# servo.net
KiCad netlist of a schematic drawn in Altium Designer
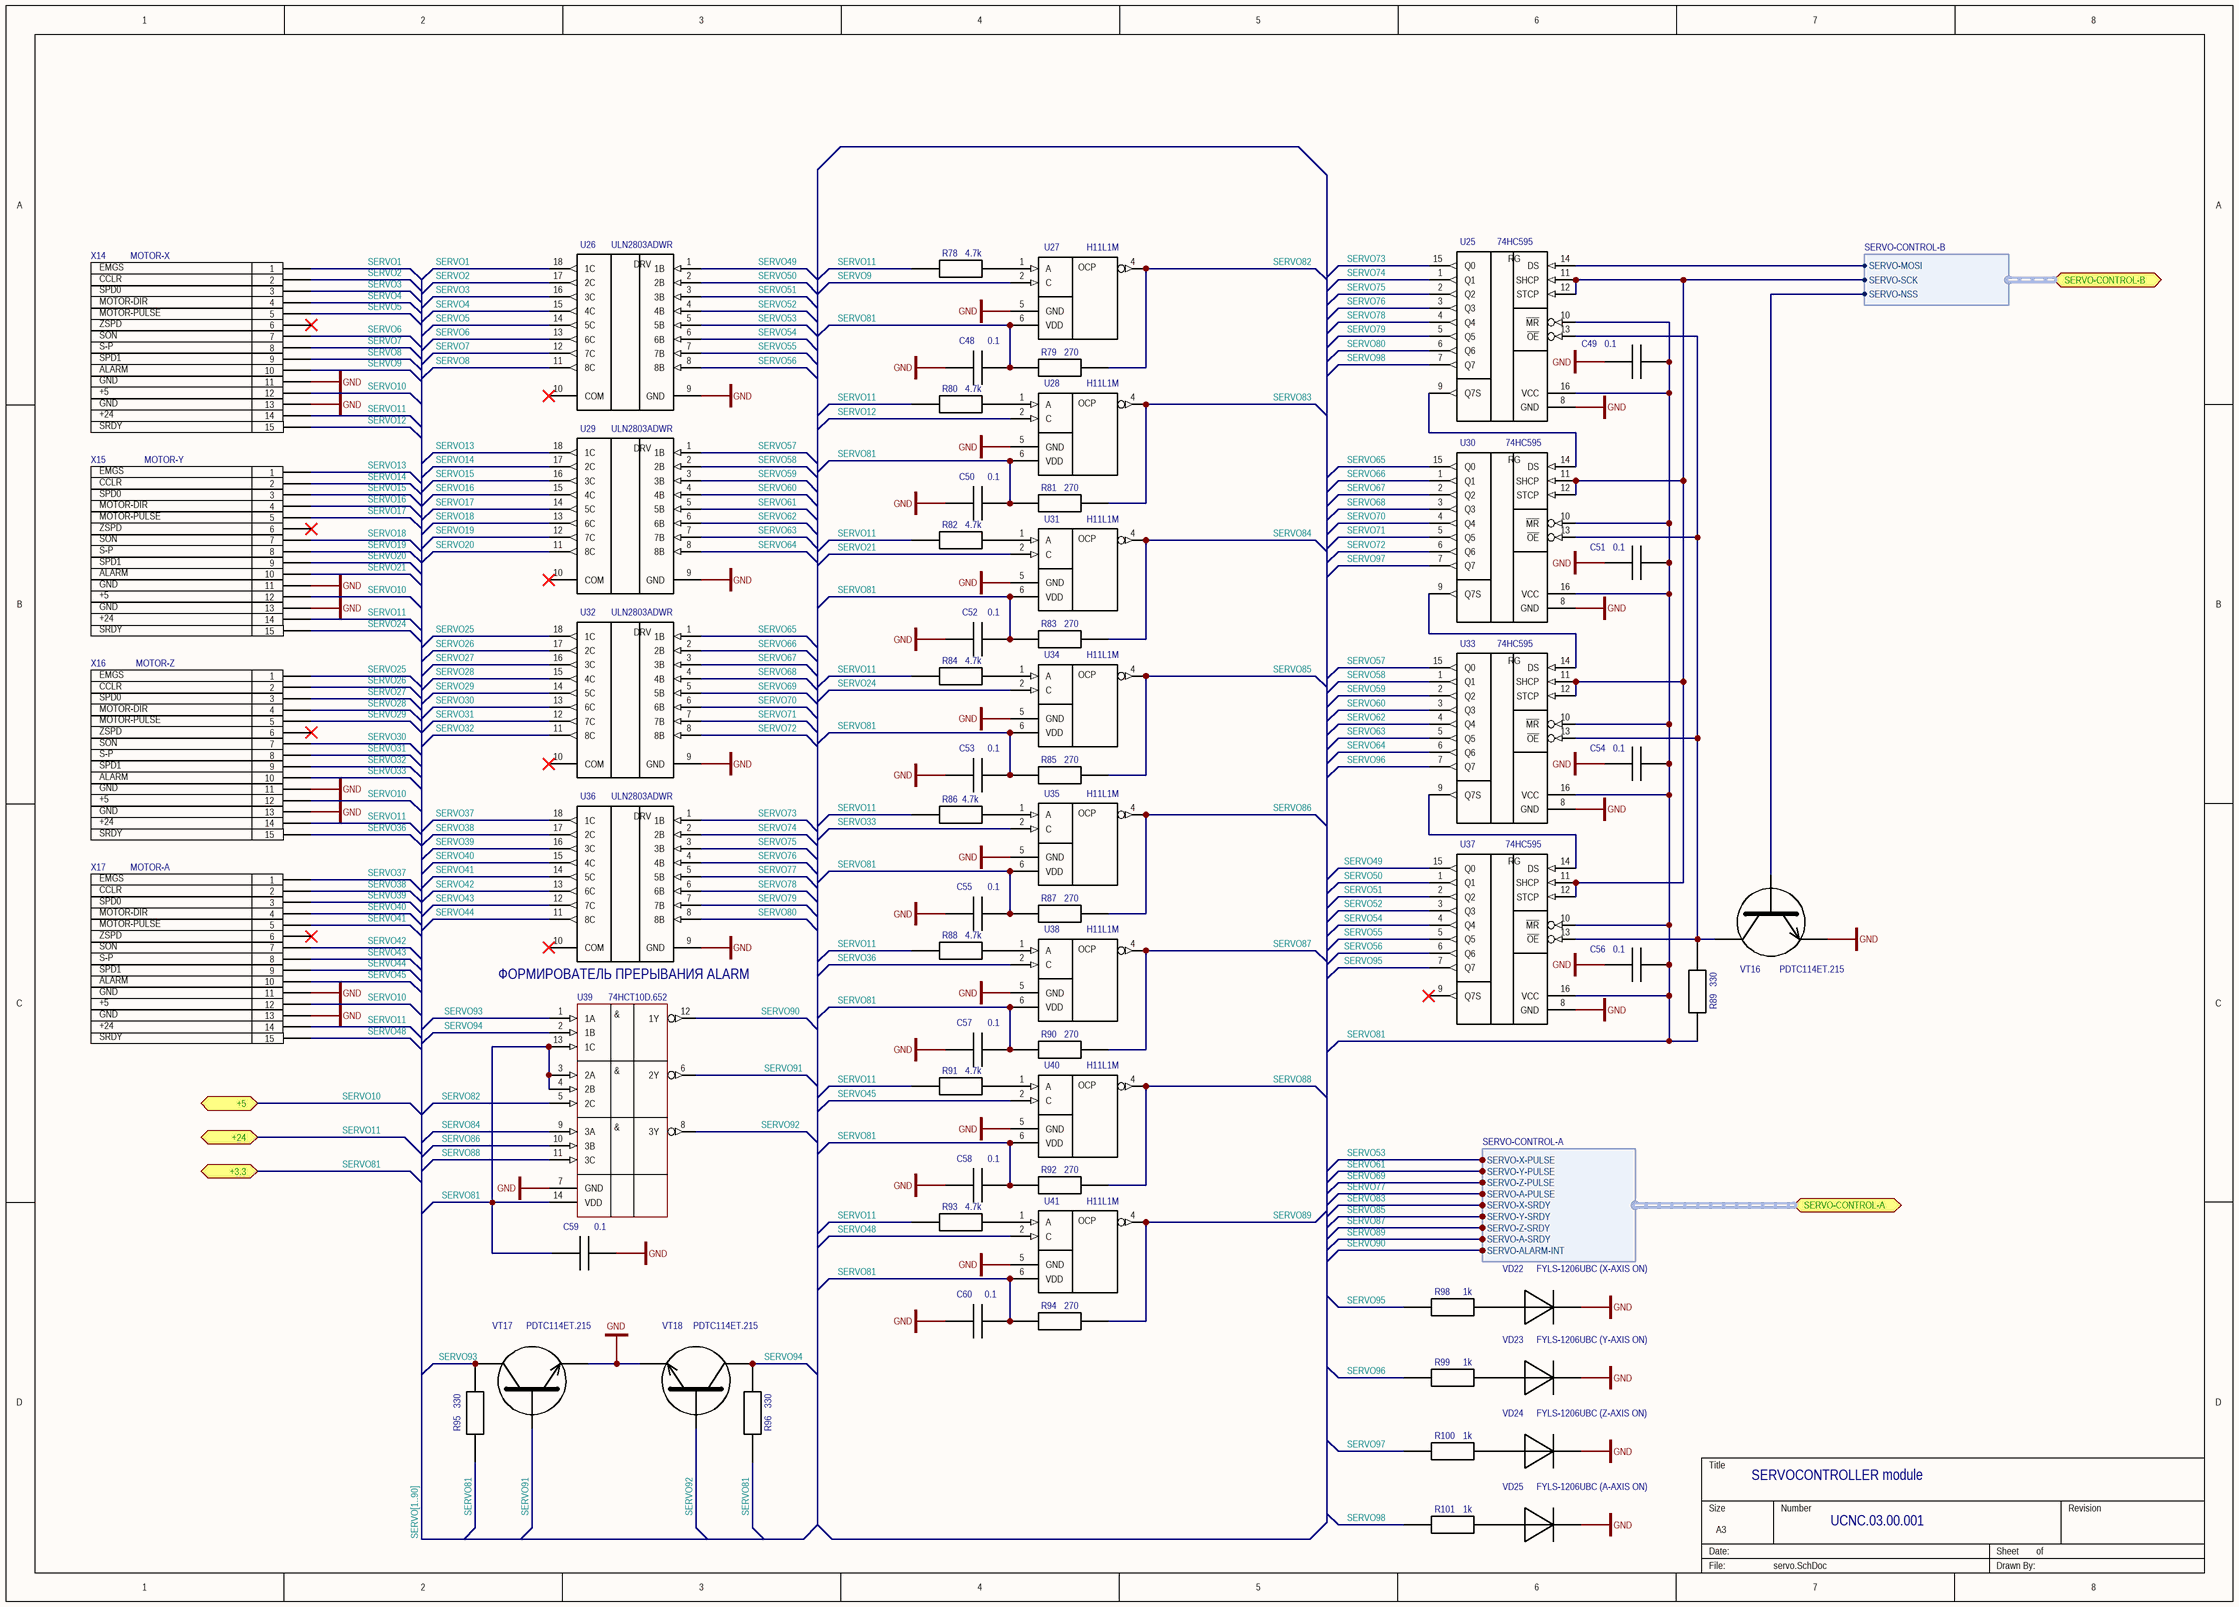
[diagram p0: servo.SchDoc]

(export (version "E")
  (design (tool "Eeschema 10.0.6"))
  (components
    (comp (ref "C48")
      (value "0.1")
      (footprint "CAPC2012X04N")
      (description "SMD конденсатор")
      (libsource (lib "ulysses_library") (part "C"))
    )
    (comp (ref "C49")
      (value "0.1")
      (footprint "CAPC2012X04N")
      (description "SMD конденсатор")
      (libsource (lib "ulysses_library") (part "C"))
    )
    (comp (ref "C50")
      (value "0.1")
      (footprint "CAPC2012X04N")
      (description "SMD конденсатор")
      (libsource (lib "ulysses_library") (part "C"))
    )
    (comp (ref "C51")
      (value "0.1")
      (footprint "CAPC2012X04N")
      (description "SMD конденсатор")
      (libsource (lib "ulysses_library") (part "C"))
    )
    (comp (ref "C52")
      (value "0.1")
      (footprint "CAPC2012X04N")
      (description "SMD конденсатор")
      (libsource (lib "ulysses_library") (part "C"))
    )
    (comp (ref "C53")
      (value "0.1")
      (footprint "CAPC2012X04N")
      (description "SMD конденсатор")
      (libsource (lib "ulysses_library") (part "C"))
    )
    (comp (ref "C54")
      (value "0.1")
      (footprint "CAPC2012X04N")
      (description "SMD конденсатор")
      (libsource (lib "ulysses_library") (part "C"))
    )
    (comp (ref "C55")
      (value "0.1")
      (footprint "CAPC2012X04N")
      (description "SMD конденсатор")
      (libsource (lib "ulysses_library") (part "C"))
    )
    (comp (ref "C56")
      (value "0.1")
      (footprint "CAPC2012X04N")
      (description "SMD конденсатор")
      (libsource (lib "ulysses_library") (part "C"))
    )
    (comp (ref "C57")
      (value "0.1")
      (footprint "CAPC2012X04N")
      (description "SMD конденсатор")
      (libsource (lib "ulysses_library") (part "C"))
    )
    (comp (ref "C58")
      (value "0.1")
      (footprint "CAPC2012X04N")
      (description "SMD конденсатор")
      (libsource (lib "ulysses_library") (part "C"))
    )
    (comp (ref "C59")
      (value "0.1")
      (footprint "CAPC2012X04N")
      (description "SMD конденсатор")
      (libsource (lib "ulysses_library") (part "C"))
    )
    (comp (ref "C60")
      (value "0.1")
      (footprint "CAPC2012X04N")
      (description "SMD конденсатор")
      (libsource (lib "ulysses_library") (part "C"))
    )
    (comp (ref "R78")
      (value "4.7k")
      (footprint "RESC2012X04N")
      (description "SMD резистор")
      (libsource (lib "ulysses_library") (part "R"))
    )
    (comp (ref "R79")
      (value "270")
      (footprint "RESC2012X04N")
      (description "SMD резистор")
      (libsource (lib "ulysses_library") (part "R"))
    )
    (comp (ref "R80")
      (value "4.7k")
      (footprint "RESC2012X04N")
      (description "SMD резистор")
      (libsource (lib "ulysses_library") (part "R"))
    )
    (comp (ref "R81")
      (value "270")
      (footprint "RESC2012X04N")
      (description "SMD резистор")
      (libsource (lib "ulysses_library") (part "R"))
    )
    (comp (ref "R82")
      (value "4.7k")
      (footprint "RESC2012X04N")
      (description "SMD резистор")
      (libsource (lib "ulysses_library") (part "R"))
    )
    (comp (ref "R83")
      (value "270")
      (footprint "RESC2012X04N")
      (description "SMD резистор")
      (libsource (lib "ulysses_library") (part "R"))
    )
    (comp (ref "R84")
      (value "4.7k")
      (footprint "RESC2012X04N")
      (description "SMD резистор")
      (libsource (lib "ulysses_library") (part "R"))
    )
    (comp (ref "R85")
      (value "270")
      (footprint "RESC2012X04N")
      (description "SMD резистор")
      (libsource (lib "ulysses_library") (part "R"))
    )
    (comp (ref "R86")
      (value "4.7k")
      (footprint "RESC2012X04N")
      (description "SMD резистор")
      (libsource (lib "ulysses_library") (part "R"))
    )
    (comp (ref "R87")
      (value "270")
      (footprint "RESC2012X04N")
      (description "SMD резистор")
      (libsource (lib "ulysses_library") (part "R"))
    )
    (comp (ref "R88")
      (value "4.7k")
      (footprint "RESC2012X04N")
      (description "SMD резистор")
      (libsource (lib "ulysses_library") (part "R"))
    )
    (comp (ref "R89")
      (value "330")
      (footprint "RESC1608X05N")
      (description "SMD резистор")
      (libsource (lib "ulysses_library") (part "R"))
    )
    (comp (ref "R90")
      (value "270")
      (footprint "RESC2012X04N")
      (description "SMD резистор")
      (libsource (lib "ulysses_library") (part "R"))
    )
    (comp (ref "R91")
      (value "4.7k")
      (footprint "RESC2012X04N")
      (description "SMD резистор")
      (libsource (lib "ulysses_library") (part "R"))
    )
    (comp (ref "R92")
      (value "270")
      (footprint "RESC2012X04N")
      (description "SMD резистор")
      (libsource (lib "ulysses_library") (part "R"))
    )
    (comp (ref "R93")
      (value "4.7k")
      (footprint "RESC2012X04N")
      (description "SMD резистор")
      (libsource (lib "ulysses_library") (part "R"))
    )
    (comp (ref "R94")
      (value "270")
      (footprint "RESC2012X04N")
      (description "SMD резистор")
      (libsource (lib "ulysses_library") (part "R"))
    )
    (comp (ref "R95")
      (value "330")
      (footprint "RESC2012X04N")
      (description "SMD резистор")
      (libsource (lib "ulysses_library") (part "R"))
    )
    (comp (ref "R96")
      (value "330")
      (footprint "RESC2012X04N")
      (description "SMD резистор")
      (libsource (lib "ulysses_library") (part "R"))
    )
    (comp (ref "R98")
      (value "1k")
      (footprint "RESC2012X04N")
      (description "SMD резистор")
      (libsource (lib "ulysses_library") (part "R"))
    )
    (comp (ref "R99")
      (value "1k")
      (footprint "RESC2012X04N")
      (description "SMD резистор")
      (libsource (lib "ulysses_library") (part "R"))
    )
    (comp (ref "R100")
      (value "1k")
      (footprint "RESC2012X04N")
      (description "SMD резистор")
      (libsource (lib "ulysses_library") (part "R"))
    )
    (comp (ref "R101")
      (value "1k")
      (footprint "RESC2012X04N")
      (description "SMD резистор")
      (libsource (lib "ulysses_library") (part "R"))
    )
    (comp (ref "U25")
      (value "74HC595")
      (footprint "SOP127P700X210-16N")
      (libsource (lib "ulysses_library") (part "74HC595"))
    )
    (comp (ref "U26")
      (value "ULN2803ADWR")
      (footprint "SOIC127P1030X265-18N")
      (description "8 Darlington transistors")
      (libsource (lib "ulysses_library") (part "ULN2803ADWR"))
    )
    (comp (ref "U27")
      (value "H11L1M")
      (footprint "DIP6")
      (description "Fairchild H11L1M Schmitt Trigger Output Optocoupler")
      (libsource (lib "ulysses_library") (part "H11L1M"))
    )
    (comp (ref "U28")
      (value "H11L1M")
      (footprint "DIP6")
      (description "Fairchild H11L1M Schmitt Trigger Output Optocoupler")
      (libsource (lib "ulysses_library") (part "H11L1M"))
    )
    (comp (ref "U29")
      (value "ULN2803ADWR")
      (footprint "SOIC127P1030X265-18N")
      (description "8 Darlington transistors")
      (libsource (lib "ulysses_library") (part "ULN2803ADWR"))
    )
    (comp (ref "U30")
      (value "74HC595")
      (footprint "SOP127P700X210-16N")
      (libsource (lib "ulysses_library") (part "74HC595"))
    )
    (comp (ref "U31")
      (value "H11L1M")
      (footprint "DIP6")
      (description "Fairchild H11L1M Schmitt Trigger Output Optocoupler")
      (libsource (lib "ulysses_library") (part "H11L1M"))
    )
    (comp (ref "U32")
      (value "ULN2803ADWR")
      (footprint "SOIC127P1030X265-18N")
      (description "8 Darlington transistors")
      (libsource (lib "ulysses_library") (part "ULN2803ADWR"))
    )
    (comp (ref "U33")
      (value "74HC595")
      (footprint "SOP127P700X210-16N")
      (libsource (lib "ulysses_library") (part "74HC595"))
    )
    (comp (ref "U34")
      (value "H11L1M")
      (footprint "DIP6")
      (description "Fairchild H11L1M Schmitt Trigger Output Optocoupler")
      (libsource (lib "ulysses_library") (part "H11L1M"))
    )
    (comp (ref "U35")
      (value "H11L1M")
      (footprint "DIP6")
      (description "Fairchild H11L1M Schmitt Trigger Output Optocoupler")
      (libsource (lib "ulysses_library") (part "H11L1M"))
    )
    (comp (ref "U36")
      (value "ULN2803ADWR")
      (footprint "SOIC127P1030X265-18N")
      (description "8 Darlington transistors")
      (libsource (lib "ulysses_library") (part "ULN2803ADWR"))
    )
    (comp (ref "U37")
      (value "74HC595")
      (footprint "SOP127P700X210-16N")
      (libsource (lib "ulysses_library") (part "74HC595"))
    )
    (comp (ref "U38")
      (value "H11L1M")
      (footprint "DIP6")
      (description "Fairchild H11L1M Schmitt Trigger Output Optocoupler")
      (libsource (lib "ulysses_library") (part "H11L1M"))
    )
    (comp (ref "U39")
      (value "74HCT10D.652")
      (footprint "SOIC127P600X175-14N")
      (libsource (lib "ulysses_library") (part "74HCT10D.652"))
    )
    (comp (ref "U40")
      (value "H11L1M")
      (footprint "DIP6")
      (description "Fairchild H11L1M Schmitt Trigger Output Optocoupler")
      (libsource (lib "ulysses_library") (part "H11L1M"))
    )
    (comp (ref "U41")
      (value "H11L1M")
      (footprint "DIP6")
      (description "Fairchild H11L1M Schmitt Trigger Output Optocoupler")
      (libsource (lib "ulysses_library") (part "H11L1M"))
    )
    (comp (ref "VD22")
      (value "FYLS-1206UBC (X-AXIS ON)")
      (footprint "CAPMP3216X11N")
      (description "Светодиод")
      (libsource (lib "ulysses_library") (part "FYLS-1206"))
    )
    (comp (ref "VD23")
      (value "FYLS-1206UBC (Y-AXIS ON)")
      (footprint "CAPMP3216X11N")
      (description "Светодиод")
      (libsource (lib "ulysses_library") (part "FYLS-1206"))
    )
    (comp (ref "VD24")
      (value "FYLS-1206UBC (Z-AXIS ON)")
      (footprint "CAPMP3216X11N")
      (description "Светодиод")
      (libsource (lib "ulysses_library") (part "FYLS-1206"))
    )
    (comp (ref "VD25")
      (value "FYLS-1206UBC (A-AXIS ON)")
      (footprint "CAPMP3216X11N")
      (description "Светодиод")
      (libsource (lib "ulysses_library") (part "FYLS-1206"))
    )
    (comp (ref "VT16")
      (value "PDTC114ET.215")
      (footprint "SOT95P238X102-3N")
      (description "NPN transistor with bias circuit")
      (libsource (lib "ulysses_library") (part "PDTC114ET.215"))
    )
    (comp (ref "VT17")
      (value "PDTC114ET.215")
      (footprint "SOT95P238X102-3N")
      (description "NPN transistor with bias circuit")
      (libsource (lib "") (part "PDTC114ET.215_1"))
    )
    (comp (ref "VT18")
      (value "PDTC114ET.215")
      (footprint "SOT95P238X102-3N")
      (description "NPN transistor with bias circuit")
      (libsource (lib "ulysses_library") (part "PDTC114ET.215"))
    )
    (comp (ref "X14")
      (value "MOTOR-X")
      (footprint "DMR15F-HD")
      (libsource (lib "ulysses_library") (part "DMR15F-HD"))
    )
    (comp (ref "X15")
      (value "MOTOR-Y")
      (footprint "DMR15F-HD")
      (libsource (lib "ulysses_library") (part "DMR15F-HD"))
    )
    (comp (ref "X16")
      (value "MOTOR-Z")
      (footprint "DMR15F-HD")
      (libsource (lib "ulysses_library") (part "DMR15F-HD"))
    )
    (comp (ref "X17")
      (value "MOTOR-A")
      (footprint "DMR15F-HD")
      (libsource (lib "ulysses_library") (part "DMR15F-HD"))
    )
  )
  (nets
    (net (code "9") (name "/SERVO-MOSI") (class "Default")
      (node (ref "U25") (pin "14") (pinfunction "DS_14") (pintype "input"))
    )
    (net (code "10") (name "/SERVO-NSS") (class "Default")
      (node (ref "VT16") (pin "1") (pinfunction "B_1") (pintype "power_in"))
    )
    (net (code "11") (name "/SERVO-SCK") (class "Default")
      (node (ref "U25") (pin "11") (pinfunction "SHCP_11") (pintype "input"))
      (node (ref "U25") (pin "12") (pinfunction "STCP_12") (pintype "input"))
      (node (ref "U30") (pin "11") (pinfunction "SHCP_11") (pintype "input"))
      (node (ref "U30") (pin "12") (pinfunction "STCP_12") (pintype "input"))
      (node (ref "U33") (pin "11") (pinfunction "SHCP_11") (pintype "input"))
      (node (ref "U33") (pin "12") (pinfunction "STCP_12") (pintype "input"))
      (node (ref "U37") (pin "11") (pinfunction "SHCP_11") (pintype "input"))
      (node (ref "U37") (pin "12") (pinfunction "STCP_12") (pintype "input"))
    )
    (net (code "12") (name "/SERVO1") (class "Default")
      (node (ref "U26") (pin "18") (pinfunction "1C_18") (pintype "output"))
      (node (ref "X14") (pin "1") (pinfunction "1_1") (pintype "passive"))
    )
    (net (code "13") (name "/SERVO2") (class "Default")
      (node (ref "U26") (pin "17") (pinfunction "2C_17") (pintype "output"))
      (node (ref "X14") (pin "2") (pinfunction "2_2") (pintype "passive"))
    )
    (net (code "14") (name "/SERVO3") (class "Default")
      (node (ref "U26") (pin "16") (pinfunction "3C_16") (pintype "output"))
      (node (ref "X14") (pin "3") (pinfunction "3_3") (pintype "passive"))
    )
    (net (code "15") (name "/SERVO4") (class "Default")
      (node (ref "U26") (pin "15") (pinfunction "4C_15") (pintype "output"))
      (node (ref "X14") (pin "4") (pinfunction "4_4") (pintype "passive"))
    )
    (net (code "16") (name "/SERVO5") (class "Default")
      (node (ref "U26") (pin "14") (pinfunction "5C_14") (pintype "output"))
      (node (ref "X14") (pin "5") (pinfunction "5_5") (pintype "passive"))
    )
    (net (code "17") (name "/SERVO6") (class "Default")
      (node (ref "U26") (pin "13") (pinfunction "6C_13") (pintype "output"))
      (node (ref "X14") (pin "7") (pinfunction "7_7") (pintype "passive"))
    )
    (net (code "18") (name "/SERVO7") (class "Default")
      (node (ref "U26") (pin "12") (pinfunction "7C_12") (pintype "output"))
      (node (ref "X14") (pin "8") (pinfunction "8_8") (pintype "passive"))
    )
    (net (code "19") (name "/SERVO8") (class "Default")
      (node (ref "U26") (pin "11") (pinfunction "8C_11") (pintype "output"))
      (node (ref "X14") (pin "9") (pinfunction "9_9") (pintype "passive"))
    )
    (net (code "20") (name "/SERVO9") (class "Default")
      (node (ref "U27") (pin "2") (pinfunction "C_2") (pintype "input"))
      (node (ref "X14") (pin "10") (pinfunction "10_10") (pintype "passive"))
    )
    (net (code "21") (name "/SERVO10") (class "Default")
      (node (ref "X14") (pin "12") (pinfunction "12_12") (pintype "passive"))
      (node (ref "X15") (pin "12") (pinfunction "12_12") (pintype "passive"))
      (node (ref "X16") (pin "12") (pinfunction "12_12") (pintype "passive"))
      (node (ref "X17") (pin "12") (pinfunction "12_12") (pintype "passive"))
    )
    (net (code "22") (name "/SERVO11") (class "Default")
      (node (ref "R78") (pin "1") (pintype "passive"))
      (node (ref "R80") (pin "1") (pintype "passive"))
      (node (ref "R82") (pin "1") (pintype "passive"))
      (node (ref "R84") (pin "1") (pintype "passive"))
      (node (ref "R86") (pin "1") (pintype "passive"))
      (node (ref "R88") (pin "1") (pintype "passive"))
      (node (ref "R91") (pin "1") (pintype "passive"))
      (node (ref "R93") (pin "1") (pintype "passive"))
      (node (ref "X14") (pin "14") (pinfunction "14_14") (pintype "passive"))
      (node (ref "X15") (pin "14") (pinfunction "14_14") (pintype "passive"))
      (node (ref "X16") (pin "14") (pinfunction "14_14") (pintype "passive"))
      (node (ref "X17") (pin "14") (pinfunction "14_14") (pintype "passive"))
    )
    (net (code "23") (name "/SERVO12") (class "Default")
      (node (ref "U28") (pin "2") (pinfunction "C_2") (pintype "input"))
      (node (ref "X14") (pin "15") (pinfunction "15_15") (pintype "passive"))
    )
    (net (code "24") (name "/SERVO13") (class "Default")
      (node (ref "U29") (pin "18") (pinfunction "1C_18") (pintype "output"))
      (node (ref "X15") (pin "1") (pinfunction "1_1") (pintype "passive"))
    )
    (net (code "25") (name "/SERVO14") (class "Default")
      (node (ref "U29") (pin "17") (pinfunction "2C_17") (pintype "output"))
      (node (ref "X15") (pin "2") (pinfunction "2_2") (pintype "passive"))
    )
    (net (code "26") (name "/SERVO15") (class "Default")
      (node (ref "U29") (pin "16") (pinfunction "3C_16") (pintype "output"))
      (node (ref "X15") (pin "3") (pinfunction "3_3") (pintype "passive"))
    )
    (net (code "27") (name "/SERVO16") (class "Default")
      (node (ref "U29") (pin "15") (pinfunction "4C_15") (pintype "output"))
      (node (ref "X15") (pin "4") (pinfunction "4_4") (pintype "passive"))
    )
    (net (code "28") (name "/SERVO17") (class "Default")
      (node (ref "U29") (pin "14") (pinfunction "5C_14") (pintype "output"))
      (node (ref "X15") (pin "5") (pinfunction "5_5") (pintype "passive"))
    )
    (net (code "29") (name "/SERVO18") (class "Default")
      (node (ref "U29") (pin "13") (pinfunction "6C_13") (pintype "output"))
      (node (ref "X15") (pin "7") (pinfunction "7_7") (pintype "passive"))
    )
    (net (code "30") (name "/SERVO19") (class "Default")
      (node (ref "U29") (pin "12") (pinfunction "7C_12") (pintype "output"))
      (node (ref "X15") (pin "8") (pinfunction "8_8") (pintype "passive"))
    )
    (net (code "31") (name "/SERVO20") (class "Default")
      (node (ref "U29") (pin "11") (pinfunction "8C_11") (pintype "output"))
      (node (ref "X15") (pin "9") (pinfunction "9_9") (pintype "passive"))
    )
    (net (code "32") (name "/SERVO21") (class "Default")
      (node (ref "U31") (pin "2") (pinfunction "C_2") (pintype "input"))
      (node (ref "X15") (pin "10") (pinfunction "10_10") (pintype "passive"))
    )
    (net (code "33") (name "/SERVO24") (class "Default")
      (node (ref "U34") (pin "2") (pinfunction "C_2") (pintype "input"))
      (node (ref "X15") (pin "15") (pinfunction "15_15") (pintype "passive"))
    )
    (net (code "34") (name "/SERVO25") (class "Default")
      (node (ref "U32") (pin "18") (pinfunction "1C_18") (pintype "output"))
      (node (ref "X16") (pin "1") (pinfunction "1_1") (pintype "passive"))
    )
    (net (code "35") (name "/SERVO26") (class "Default")
      (node (ref "U32") (pin "17") (pinfunction "2C_17") (pintype "output"))
      (node (ref "X16") (pin "2") (pinfunction "2_2") (pintype "passive"))
    )
    (net (code "36") (name "/SERVO27") (class "Default")
      (node (ref "U32") (pin "16") (pinfunction "3C_16") (pintype "output"))
      (node (ref "X16") (pin "3") (pinfunction "3_3") (pintype "passive"))
    )
    (net (code "37") (name "/SERVO28") (class "Default")
      (node (ref "U32") (pin "15") (pinfunction "4C_15") (pintype "output"))
      (node (ref "X16") (pin "4") (pinfunction "4_4") (pintype "passive"))
    )
    (net (code "38") (name "/SERVO29") (class "Default")
      (node (ref "U32") (pin "14") (pinfunction "5C_14") (pintype "output"))
      (node (ref "X16") (pin "5") (pinfunction "5_5") (pintype "passive"))
    )
    (net (code "39") (name "/SERVO30") (class "Default")
      (node (ref "U32") (pin "13") (pinfunction "6C_13") (pintype "output"))
      (node (ref "X16") (pin "7") (pinfunction "7_7") (pintype "passive"))
    )
    (net (code "40") (name "/SERVO31") (class "Default")
      (node (ref "U32") (pin "12") (pinfunction "7C_12") (pintype "output"))
      (node (ref "X16") (pin "8") (pinfunction "8_8") (pintype "passive"))
    )
    (net (code "41") (name "/SERVO32") (class "Default")
      (node (ref "U32") (pin "11") (pinfunction "8C_11") (pintype "output"))
      (node (ref "X16") (pin "9") (pinfunction "9_9") (pintype "passive"))
    )
    (net (code "42") (name "/SERVO33") (class "Default")
      (node (ref "U35") (pin "2") (pinfunction "C_2") (pintype "input"))
      (node (ref "X16") (pin "10") (pinfunction "10_10") (pintype "passive"))
    )
    (net (code "43") (name "/SERVO36") (class "Default")
      (node (ref "U38") (pin "2") (pinfunction "C_2") (pintype "input"))
      (node (ref "X16") (pin "15") (pinfunction "15_15") (pintype "passive"))
    )
    (net (code "44") (name "/SERVO37") (class "Default")
      (node (ref "U36") (pin "18") (pinfunction "1C_18") (pintype "output"))
      (node (ref "X17") (pin "1") (pinfunction "1_1") (pintype "passive"))
    )
    (net (code "45") (name "/SERVO38") (class "Default")
      (node (ref "U36") (pin "17") (pinfunction "2C_17") (pintype "output"))
      (node (ref "X17") (pin "2") (pinfunction "2_2") (pintype "passive"))
    )
    (net (code "46") (name "/SERVO39") (class "Default")
      (node (ref "U36") (pin "16") (pinfunction "3C_16") (pintype "output"))
      (node (ref "X17") (pin "3") (pinfunction "3_3") (pintype "passive"))
    )
    (net (code "47") (name "/SERVO40") (class "Default")
      (node (ref "U36") (pin "15") (pinfunction "4C_15") (pintype "output"))
      (node (ref "X17") (pin "4") (pinfunction "4_4") (pintype "passive"))
    )
    (net (code "48") (name "/SERVO41") (class "Default")
      (node (ref "U36") (pin "14") (pinfunction "5C_14") (pintype "output"))
      (node (ref "X17") (pin "5") (pinfunction "5_5") (pintype "passive"))
    )
    (net (code "49") (name "/SERVO42") (class "Default")
      (node (ref "U36") (pin "13") (pinfunction "6C_13") (pintype "output"))
      (node (ref "X17") (pin "7") (pinfunction "7_7") (pintype "passive"))
    )
    (net (code "50") (name "/SERVO43") (class "Default")
      (node (ref "U36") (pin "12") (pinfunction "7C_12") (pintype "output"))
      (node (ref "X17") (pin "8") (pinfunction "8_8") (pintype "passive"))
    )
    (net (code "51") (name "/SERVO44") (class "Default")
      (node (ref "U36") (pin "11") (pinfunction "8C_11") (pintype "output"))
      (node (ref "X17") (pin "9") (pinfunction "9_9") (pintype "passive"))
    )
    (net (code "52") (name "/SERVO45") (class "Default")
      (node (ref "U40") (pin "2") (pinfunction "C_2") (pintype "input"))
      (node (ref "X17") (pin "10") (pinfunction "10_10") (pintype "passive"))
    )
    (net (code "53") (name "/SERVO48") (class "Default")
      (node (ref "U41") (pin "2") (pinfunction "C_2") (pintype "input"))
      (node (ref "X17") (pin "15") (pinfunction "15_15") (pintype "passive"))
    )
    (net (code "54") (name "/SERVO49") (class "Default")
      (node (ref "U26") (pin "1") (pinfunction "1B_1") (pintype "input"))
      (node (ref "U37") (pin "15") (pinfunction "Q0_15") (pintype "output"))
    )
    (net (code "55") (name "/SERVO50") (class "Default")
      (node (ref "U26") (pin "2") (pinfunction "2B_2") (pintype "input"))
      (node (ref "U37") (pin "1") (pinfunction "Q1_1") (pintype "output"))
    )
    (net (code "56") (name "/SERVO51") (class "Default")
      (node (ref "U26") (pin "3") (pinfunction "3B_3") (pintype "input"))
      (node (ref "U37") (pin "2") (pinfunction "Q2_2") (pintype "output"))
    )
    (net (code "57") (name "/SERVO52") (class "Default")
      (node (ref "U26") (pin "4") (pinfunction "4B_4") (pintype "input"))
      (node (ref "U37") (pin "3") (pinfunction "Q3_3") (pintype "output"))
    )
    (net (code "58") (name "/SERVO53") (class "Default")
      (node (ref "U26") (pin "5") (pinfunction "5B_5") (pintype "input"))
    )
    (net (code "59") (name "/SERVO54") (class "Default")
      (node (ref "U26") (pin "6") (pinfunction "6B_6") (pintype "input"))
      (node (ref "U37") (pin "4") (pinfunction "Q4_4") (pintype "output"))
    )
    (net (code "60") (name "/SERVO55") (class "Default")
      (node (ref "U26") (pin "7") (pinfunction "7B_7") (pintype "input"))
      (node (ref "U37") (pin "5") (pinfunction "Q5_5") (pintype "output"))
    )
    (net (code "61") (name "/SERVO56") (class "Default")
      (node (ref "U26") (pin "8") (pinfunction "8B_8") (pintype "input"))
      (node (ref "U37") (pin "6") (pinfunction "Q6_6") (pintype "output"))
    )
    (net (code "62") (name "/SERVO57") (class "Default")
      (node (ref "U29") (pin "1") (pinfunction "1B_1") (pintype "input"))
      (node (ref "U33") (pin "15") (pinfunction "Q0_15") (pintype "output"))
    )
    (net (code "63") (name "/SERVO58") (class "Default")
      (node (ref "U29") (pin "2") (pinfunction "2B_2") (pintype "input"))
      (node (ref "U33") (pin "1") (pinfunction "Q1_1") (pintype "output"))
    )
    (net (code "64") (name "/SERVO59") (class "Default")
      (node (ref "U29") (pin "3") (pinfunction "3B_3") (pintype "input"))
      (node (ref "U33") (pin "2") (pinfunction "Q2_2") (pintype "output"))
    )
    (net (code "65") (name "/SERVO60") (class "Default")
      (node (ref "U29") (pin "4") (pinfunction "4B_4") (pintype "input"))
      (node (ref "U33") (pin "3") (pinfunction "Q3_3") (pintype "output"))
    )
    (net (code "66") (name "/SERVO61") (class "Default")
      (node (ref "U29") (pin "5") (pinfunction "5B_5") (pintype "input"))
    )
    (net (code "67") (name "/SERVO62") (class "Default")
      (node (ref "U29") (pin "6") (pinfunction "6B_6") (pintype "input"))
      (node (ref "U33") (pin "4") (pinfunction "Q4_4") (pintype "output"))
    )
    (net (code "68") (name "/SERVO63") (class "Default")
      (node (ref "U29") (pin "7") (pinfunction "7B_7") (pintype "input"))
      (node (ref "U33") (pin "5") (pinfunction "Q5_5") (pintype "output"))
    )
    (net (code "69") (name "/SERVO64") (class "Default")
      (node (ref "U29") (pin "8") (pinfunction "8B_8") (pintype "input"))
      (node (ref "U33") (pin "6") (pinfunction "Q6_6") (pintype "output"))
    )
    (net (code "70") (name "/SERVO65") (class "Default")
      (node (ref "U30") (pin "15") (pinfunction "Q0_15") (pintype "output"))
      (node (ref "U32") (pin "1") (pinfunction "1B_1") (pintype "input"))
    )
    (net (code "71") (name "/SERVO66") (class "Default")
      (node (ref "U30") (pin "1") (pinfunction "Q1_1") (pintype "output"))
      (node (ref "U32") (pin "2") (pinfunction "2B_2") (pintype "input"))
    )
    (net (code "72") (name "/SERVO67") (class "Default")
      (node (ref "U30") (pin "2") (pinfunction "Q2_2") (pintype "output"))
      (node (ref "U32") (pin "3") (pinfunction "3B_3") (pintype "input"))
    )
    (net (code "73") (name "/SERVO68") (class "Default")
      (node (ref "U30") (pin "3") (pinfunction "Q3_3") (pintype "output"))
      (node (ref "U32") (pin "4") (pinfunction "4B_4") (pintype "input"))
    )
    (net (code "74") (name "/SERVO69") (class "Default")
      (node (ref "U32") (pin "5") (pinfunction "5B_5") (pintype "input"))
    )
    (net (code "75") (name "/SERVO70") (class "Default")
      (node (ref "U30") (pin "4") (pinfunction "Q4_4") (pintype "output"))
      (node (ref "U32") (pin "6") (pinfunction "6B_6") (pintype "input"))
    )
    (net (code "76") (name "/SERVO71") (class "Default")
      (node (ref "U30") (pin "5") (pinfunction "Q5_5") (pintype "output"))
      (node (ref "U32") (pin "7") (pinfunction "7B_7") (pintype "input"))
    )
    (net (code "77") (name "/SERVO72") (class "Default")
      (node (ref "U30") (pin "6") (pinfunction "Q6_6") (pintype "output"))
      (node (ref "U32") (pin "8") (pinfunction "8B_8") (pintype "input"))
    )
    (net (code "78") (name "/SERVO73") (class "Default")
      (node (ref "U25") (pin "15") (pinfunction "Q0_15") (pintype "output"))
      (node (ref "U36") (pin "1") (pinfunction "1B_1") (pintype "input"))
    )
    (net (code "79") (name "/SERVO74") (class "Default")
      (node (ref "U25") (pin "1") (pinfunction "Q1_1") (pintype "output"))
      (node (ref "U36") (pin "2") (pinfunction "2B_2") (pintype "input"))
    )
    (net (code "80") (name "/SERVO75") (class "Default")
      (node (ref "U25") (pin "2") (pinfunction "Q2_2") (pintype "output"))
      (node (ref "U36") (pin "3") (pinfunction "3B_3") (pintype "input"))
    )
    (net (code "81") (name "/SERVO76") (class "Default")
      (node (ref "U25") (pin "3") (pinfunction "Q3_3") (pintype "output"))
      (node (ref "U36") (pin "4") (pinfunction "4B_4") (pintype "input"))
    )
    (net (code "82") (name "/SERVO77") (class "Default")
      (node (ref "U36") (pin "5") (pinfunction "5B_5") (pintype "input"))
    )
    (net (code "83") (name "/SERVO78") (class "Default")
      (node (ref "U25") (pin "4") (pinfunction "Q4_4") (pintype "output"))
      (node (ref "U36") (pin "6") (pinfunction "6B_6") (pintype "input"))
    )
    (net (code "84") (name "/SERVO79") (class "Default")
      (node (ref "U25") (pin "5") (pinfunction "Q5_5") (pintype "output"))
      (node (ref "U36") (pin "7") (pinfunction "7B_7") (pintype "input"))
    )
    (net (code "85") (name "/SERVO80") (class "Default")
      (node (ref "U25") (pin "6") (pinfunction "Q6_6") (pintype "output"))
      (node (ref "U36") (pin "8") (pinfunction "8B_8") (pintype "input"))
    )
    (net (code "86") (name "/SERVO81") (class "Default")
      (node (ref "C48") (pin "2") (pinfunction "2_2") (pintype "passive"))
      (node (ref "C49") (pin "1") (pinfunction "1_1") (pintype "passive"))
      (node (ref "C50") (pin "2") (pinfunction "2_2") (pintype "passive"))
      (node (ref "C51") (pin "1") (pinfunction "1_1") (pintype "passive"))
      (node (ref "C52") (pin "2") (pinfunction "2_2") (pintype "passive"))
      (node (ref "C53") (pin "2") (pinfunction "2_2") (pintype "passive"))
      (node (ref "C54") (pin "1") (pinfunction "1_1") (pintype "passive"))
      (node (ref "C55") (pin "2") (pinfunction "2_2") (pintype "passive"))
      (node (ref "C56") (pin "1") (pinfunction "1_1") (pintype "passive"))
      (node (ref "C57") (pin "2") (pinfunction "2_2") (pintype "passive"))
      (node (ref "C58") (pin "2") (pinfunction "2_2") (pintype "passive"))
      (node (ref "C59") (pin "1") (pinfunction "1_1") (pintype "passive"))
      (node (ref "C60") (pin "2") (pinfunction "2_2") (pintype "passive"))
      (node (ref "R79") (pin "1") (pintype "passive"))
      (node (ref "R81") (pin "1") (pintype "passive"))
      (node (ref "R83") (pin "1") (pintype "passive"))
      (node (ref "R85") (pin "1") (pintype "passive"))
      (node (ref "R87") (pin "1") (pintype "passive"))
      (node (ref "R89") (pin "1") (pintype "passive"))
      (node (ref "R90") (pin "1") (pintype "passive"))
      (node (ref "R92") (pin "1") (pintype "passive"))
      (node (ref "R94") (pin "1") (pintype "passive"))
      (node (ref "R95") (pin "1") (pintype "passive"))
      (node (ref "R96") (pin "1") (pintype "passive"))
      (node (ref "U25") (pin "10") (pinfunction "~{MR}_10") (pintype "input"))
      (node (ref "U25") (pin "16") (pinfunction "VCC_16") (pintype "power_in"))
      (node (ref "U27") (pin "6") (pinfunction "VDD_6") (pintype "power_in"))
      (node (ref "U28") (pin "6") (pinfunction "VDD_6") (pintype "power_in"))
      (node (ref "U30") (pin "10") (pinfunction "~{MR}_10") (pintype "input"))
      (node (ref "U30") (pin "16") (pinfunction "VCC_16") (pintype "power_in"))
      (node (ref "U31") (pin "6") (pinfunction "VDD_6") (pintype "power_in"))
      (node (ref "U33") (pin "10") (pinfunction "~{MR}_10") (pintype "input"))
      (node (ref "U33") (pin "16") (pinfunction "VCC_16") (pintype "power_in"))
      (node (ref "U34") (pin "6") (pinfunction "VDD_6") (pintype "power_in"))
      (node (ref "U35") (pin "6") (pinfunction "VDD_6") (pintype "power_in"))
      (node (ref "U37") (pin "10") (pinfunction "~{MR}_10") (pintype "input"))
      (node (ref "U37") (pin "16") (pinfunction "VCC_16") (pintype "power_in"))
      (node (ref "U38") (pin "6") (pinfunction "VDD_6") (pintype "power_in"))
      (node (ref "U39") (pin "13") (pinfunction "1C_13") (pintype "input"))
      (node (ref "U39") (pin "14") (pinfunction "VDD_14") (pintype "power_in"))
      (node (ref "U39") (pin "3") (pinfunction "2A_3") (pintype "input"))
      (node (ref "U39") (pin "4") (pinfunction "2B_4") (pintype "input"))
      (node (ref "U40") (pin "6") (pinfunction "VDD_6") (pintype "power_in"))
      (node (ref "U41") (pin "6") (pinfunction "VDD_6") (pintype "power_in"))
    )
    (net (code "87") (name "/SERVO82") (class "Default")
      (node (ref "R79") (pin "2") (pinfunction "2_2") (pintype "passive"))
      (node (ref "U27") (pin "4") (pinfunction "OUT_4") (pintype "output"))
      (node (ref "U39") (pin "5") (pinfunction "2C_5") (pintype "input"))
    )
    (net (code "88") (name "/SERVO83") (class "Default")
      (node (ref "R81") (pin "2") (pinfunction "2_2") (pintype "passive"))
      (node (ref "U28") (pin "4") (pinfunction "OUT_4") (pintype "output"))
    )
    (net (code "89") (name "/SERVO84") (class "Default")
      (node (ref "R83") (pin "2") (pinfunction "2_2") (pintype "passive"))
      (node (ref "U31") (pin "4") (pinfunction "OUT_4") (pintype "output"))
      (node (ref "U39") (pin "9") (pinfunction "3A_9") (pintype "input"))
    )
    (net (code "90") (name "/SERVO85") (class "Default")
      (node (ref "R85") (pin "2") (pinfunction "2_2") (pintype "passive"))
      (node (ref "U34") (pin "4") (pinfunction "OUT_4") (pintype "output"))
    )
    (net (code "91") (name "/SERVO86") (class "Default")
      (node (ref "R87") (pin "2") (pinfunction "2_2") (pintype "passive"))
      (node (ref "U35") (pin "4") (pinfunction "OUT_4") (pintype "output"))
      (node (ref "U39") (pin "10") (pinfunction "3B_10") (pintype "input"))
    )
    (net (code "92") (name "/SERVO87") (class "Default")
      (node (ref "R90") (pin "2") (pinfunction "2_2") (pintype "passive"))
      (node (ref "U38") (pin "4") (pinfunction "OUT_4") (pintype "output"))
    )
    (net (code "93") (name "/SERVO88") (class "Default")
      (node (ref "R92") (pin "2") (pinfunction "2_2") (pintype "passive"))
      (node (ref "U39") (pin "11") (pinfunction "3C_11") (pintype "input"))
      (node (ref "U40") (pin "4") (pinfunction "OUT_4") (pintype "output"))
    )
    (net (code "94") (name "/SERVO89") (class "Default")
      (node (ref "R94") (pin "2") (pinfunction "2_2") (pintype "passive"))
      (node (ref "U41") (pin "4") (pinfunction "OUT_4") (pintype "output"))
    )
    (net (code "95") (name "/SERVO90") (class "Default")
      (node (ref "U39") (pin "12") (pinfunction "1Y_12") (pintype "output"))
    )
    (net (code "96") (name "/SERVO91") (class "Default")
      (node (ref "U39") (pin "6") (pinfunction "2Y_6") (pintype "output"))
      (node (ref "VT17") (pin "1") (pinfunction "B_1") (pintype "power_in"))
    )
    (net (code "97") (name "/SERVO92") (class "Default")
      (node (ref "U39") (pin "8") (pinfunction "3Y_8") (pintype "output"))
      (node (ref "VT18") (pin "1") (pinfunction "B_1") (pintype "power_in"))
    )
    (net (code "98") (name "/SERVO93") (class "Default")
      (node (ref "R95") (pin "2") (pinfunction "2_2") (pintype "passive"))
      (node (ref "U39") (pin "1") (pinfunction "1A_1") (pintype "input"))
      (node (ref "VT17") (pin "3") (pinfunction "C_3") (pintype "power_in"))
    )
    (net (code "99") (name "/SERVO94") (class "Default")
      (node (ref "R96") (pin "2") (pinfunction "2_2") (pintype "passive"))
      (node (ref "U39") (pin "2") (pinfunction "1B_2") (pintype "input"))
      (node (ref "VT18") (pin "3") (pinfunction "C_3") (pintype "power_in"))
    )
    (net (code "100") (name "/SERVO95") (class "Default")
      (node (ref "R98") (pin "2") (pinfunction "2_2") (pintype "passive"))
      (node (ref "U37") (pin "7") (pinfunction "Q7_7") (pintype "output"))
    )
    (net (code "101") (name "/SERVO96") (class "Default")
      (node (ref "R99") (pin "2") (pinfunction "2_2") (pintype "passive"))
      (node (ref "U33") (pin "7") (pinfunction "Q7_7") (pintype "output"))
    )
    (net (code "102") (name "/SERVO97") (class "Default")
      (node (ref "R100") (pin "2") (pinfunction "2_2") (pintype "passive"))
      (node (ref "U30") (pin "7") (pinfunction "Q7_7") (pintype "output"))
    )
    (net (code "103") (name "/SERVO98") (class "Default")
      (node (ref "R101") (pin "2") (pinfunction "2_2") (pintype "passive"))
      (node (ref "U25") (pin "7") (pinfunction "Q7_7") (pintype "output"))
    )
    (net (code "107") (name "GND") (class "Default")
      (node (ref "C48") (pin "1") (pinfunction "1_1") (pintype "passive"))
      (node (ref "C49") (pin "2") (pinfunction "2_2") (pintype "passive"))
      (node (ref "C50") (pin "1") (pinfunction "1_1") (pintype "passive"))
      (node (ref "C51") (pin "2") (pinfunction "2_2") (pintype "passive"))
      (node (ref "C52") (pin "1") (pinfunction "1_1") (pintype "passive"))
      (node (ref "C53") (pin "1") (pinfunction "1_1") (pintype "passive"))
      (node (ref "C54") (pin "2") (pinfunction "2_2") (pintype "passive"))
      (node (ref "C55") (pin "1") (pinfunction "1_1") (pintype "passive"))
      (node (ref "C56") (pin "2") (pinfunction "2_2") (pintype "passive"))
      (node (ref "C57") (pin "1") (pinfunction "1_1") (pintype "passive"))
      (node (ref "C58") (pin "1") (pinfunction "1_1") (pintype "passive"))
      (node (ref "C59") (pin "2") (pinfunction "2_2") (pintype "passive"))
      (node (ref "C60") (pin "1") (pinfunction "1_1") (pintype "passive"))
      (node (ref "U25") (pin "8") (pinfunction "GND_8") (pintype "power_in"))
      (node (ref "U26") (pin "9") (pinfunction "GND_9") (pintype "power_in"))
      (node (ref "U27") (pin "5") (pinfunction "GND_5") (pintype "power_in"))
      (node (ref "U28") (pin "5") (pinfunction "GND_5") (pintype "power_in"))
      (node (ref "U29") (pin "9") (pinfunction "GND_9") (pintype "power_in"))
      (node (ref "U30") (pin "8") (pinfunction "GND_8") (pintype "power_in"))
      (node (ref "U31") (pin "5") (pinfunction "GND_5") (pintype "power_in"))
      (node (ref "U32") (pin "9") (pinfunction "GND_9") (pintype "power_in"))
      (node (ref "U33") (pin "8") (pinfunction "GND_8") (pintype "power_in"))
      (node (ref "U34") (pin "5") (pinfunction "GND_5") (pintype "power_in"))
      (node (ref "U35") (pin "5") (pinfunction "GND_5") (pintype "power_in"))
      (node (ref "U36") (pin "9") (pinfunction "GND_9") (pintype "power_in"))
      (node (ref "U37") (pin "8") (pinfunction "GND_8") (pintype "power_in"))
      (node (ref "U38") (pin "5") (pinfunction "GND_5") (pintype "power_in"))
      (node (ref "U39") (pin "7") (pinfunction "GND_7") (pintype "power_in"))
      (node (ref "U40") (pin "5") (pinfunction "GND_5") (pintype "power_in"))
      (node (ref "U41") (pin "5") (pinfunction "GND_5") (pintype "power_in"))
      (node (ref "VD22") (pin "1") (pinfunction "C_1") (pintype "power_in"))
      (node (ref "VD23") (pin "1") (pinfunction "C_1") (pintype "power_in"))
      (node (ref "VD24") (pin "1") (pinfunction "C_1") (pintype "power_in"))
      (node (ref "VD25") (pin "1") (pinfunction "C_1") (pintype "power_in"))
      (node (ref "VT16") (pin "2") (pinfunction "E_2") (pintype "power_in"))
      (node (ref "VT17") (pin "2") (pinfunction "E_2") (pintype "power_in"))
      (node (ref "VT18") (pin "2") (pinfunction "E_2") (pintype "power_in"))
      (node (ref "X14") (pin "11") (pinfunction "11_11") (pintype "passive"))
      (node (ref "X14") (pin "13") (pinfunction "13_13") (pintype "passive"))
      (node (ref "X15") (pin "11") (pinfunction "11_11") (pintype "passive"))
      (node (ref "X15") (pin "13") (pinfunction "13_13") (pintype "passive"))
      (node (ref "X16") (pin "11") (pinfunction "11_11") (pintype "passive"))
      (node (ref "X16") (pin "13") (pinfunction "13_13") (pintype "passive"))
      (node (ref "X17") (pin "11") (pinfunction "11_11") (pintype "passive"))
      (node (ref "X17") (pin "13") (pinfunction "13_13") (pintype "passive"))
    )
    (net (code "108") (name "Net-(U25-Q7S)") (class "Default")
      (node (ref "U25") (pin "9") (pinfunction "Q7S_9") (pintype "output"))
      (node (ref "U30") (pin "14") (pinfunction "DS_14") (pintype "input"))
    )
    (net (code "109") (name "Net-(U25-~{OE})") (class "Default")
      (node (ref "R89") (pin "2") (pinfunction "2_2") (pintype "passive"))
      (node (ref "U25") (pin "13") (pinfunction "~{OE}_13") (pintype "input"))
      (node (ref "U30") (pin "13") (pinfunction "~{OE}_13") (pintype "input"))
      (node (ref "U33") (pin "13") (pinfunction "~{OE}_13") (pintype "input"))
      (node (ref "U37") (pin "13") (pinfunction "~{OE}_13") (pintype "input"))
      (node (ref "VT16") (pin "3") (pinfunction "C_3") (pintype "power_in"))
    )
    (net (code "110") (name "Net-(U27-A)") (class "Default")
      (node (ref "R78") (pin "2") (pinfunction "2_2") (pintype "passive"))
      (node (ref "U27") (pin "1") (pinfunction "A_1") (pintype "input"))
    )
    (net (code "111") (name "Net-(U28-A)") (class "Default")
      (node (ref "R80") (pin "2") (pinfunction "2_2") (pintype "passive"))
      (node (ref "U28") (pin "1") (pinfunction "A_1") (pintype "input"))
    )
    (net (code "112") (name "Net-(U30-Q7S)") (class "Default")
      (node (ref "U30") (pin "9") (pinfunction "Q7S_9") (pintype "output"))
      (node (ref "U33") (pin "14") (pinfunction "DS_14") (pintype "input"))
    )
    (net (code "113") (name "Net-(U31-A)") (class "Default")
      (node (ref "R82") (pin "2") (pinfunction "2_2") (pintype "passive"))
      (node (ref "U31") (pin "1") (pinfunction "A_1") (pintype "input"))
    )
    (net (code "114") (name "Net-(U33-Q7S)") (class "Default")
      (node (ref "U33") (pin "9") (pinfunction "Q7S_9") (pintype "output"))
      (node (ref "U37") (pin "14") (pinfunction "DS_14") (pintype "input"))
    )
    (net (code "115") (name "Net-(U34-A)") (class "Default")
      (node (ref "R84") (pin "2") (pinfunction "2_2") (pintype "passive"))
      (node (ref "U34") (pin "1") (pinfunction "A_1") (pintype "input"))
    )
    (net (code "116") (name "Net-(U35-A)") (class "Default")
      (node (ref "R86") (pin "2") (pinfunction "2_2") (pintype "passive"))
      (node (ref "U35") (pin "1") (pinfunction "A_1") (pintype "input"))
    )
    (net (code "117") (name "Net-(U38-A)") (class "Default")
      (node (ref "R88") (pin "2") (pinfunction "2_2") (pintype "passive"))
      (node (ref "U38") (pin "1") (pinfunction "A_1") (pintype "input"))
    )
    (net (code "118") (name "Net-(U40-A)") (class "Default")
      (node (ref "R91") (pin "2") (pinfunction "2_2") (pintype "passive"))
      (node (ref "U40") (pin "1") (pinfunction "A_1") (pintype "input"))
    )
    (net (code "119") (name "Net-(U41-A)") (class "Default")
      (node (ref "R93") (pin "2") (pinfunction "2_2") (pintype "passive"))
      (node (ref "U41") (pin "1") (pinfunction "A_1") (pintype "input"))
    )
    (net (code "120") (name "Net-(VD22-A)") (class "Default")
      (node (ref "R98") (pin "1") (pintype "passive"))
      (node (ref "VD22") (pin "2") (pinfunction "A_2") (pintype "power_in"))
    )
    (net (code "121") (name "Net-(VD23-A)") (class "Default")
      (node (ref "R99") (pin "1") (pintype "passive"))
      (node (ref "VD23") (pin "2") (pinfunction "A_2") (pintype "power_in"))
    )
    (net (code "122") (name "Net-(VD24-A)") (class "Default")
      (node (ref "R100") (pin "1") (pintype "passive"))
      (node (ref "VD24") (pin "2") (pinfunction "A_2") (pintype "power_in"))
    )
    (net (code "123") (name "Net-(VD25-A)") (class "Default")
      (node (ref "R101") (pin "1") (pintype "passive"))
      (node (ref "VD25") (pin "2") (pinfunction "A_2") (pintype "power_in"))
    )
    (net (code "124") (name "unconnected-(U26-COM-Pad10)") (class "Default")
      (node (ref "U26") (pin "10") (pinfunction "COM_10") (pintype "power_in+no_connect"))
    )
    (net (code "125") (name "unconnected-(U29-COM-Pad10)") (class "Default")
      (node (ref "U29") (pin "10") (pinfunction "COM_10") (pintype "power_in+no_connect"))
    )
    (net (code "126") (name "unconnected-(U32-COM-Pad10)") (class "Default")
      (node (ref "U32") (pin "10") (pinfunction "COM_10") (pintype "power_in+no_connect"))
    )
    (net (code "127") (name "unconnected-(U36-COM-Pad10)") (class "Default")
      (node (ref "U36") (pin "10") (pinfunction "COM_10") (pintype "power_in+no_connect"))
    )
    (net (code "128") (name "unconnected-(U37-Q7S-Pad9)") (class "Default")
      (node (ref "U37") (pin "9") (pinfunction "Q7S_9") (pintype "output+no_connect"))
    )
    (net (code "129") (name "unconnected-(X14-Pad6)") (class "Default")
      (node (ref "X14") (pin "6") (pinfunction "6_6") (pintype "passive+no_connect"))
    )
    (net (code "130") (name "unconnected-(X15-Pad6)") (class "Default")
      (node (ref "X15") (pin "6") (pinfunction "6_6") (pintype "passive+no_connect"))
    )
    (net (code "131") (name "unconnected-(X16-Pad6)") (class "Default")
      (node (ref "X16") (pin "6") (pinfunction "6_6") (pintype "passive+no_connect"))
    )
    (net (code "132") (name "unconnected-(X17-Pad6)") (class "Default")
      (node (ref "X17") (pin "6") (pinfunction "6_6") (pintype "passive+no_connect"))
    )
  )
)
